# Oscillator.net
KiCad netlist of a schematic drawn in Altium Designer
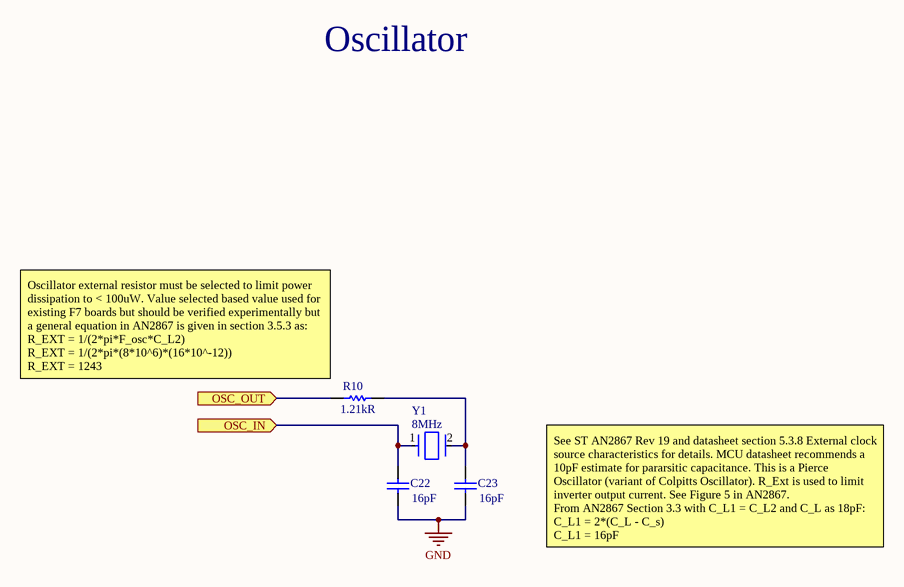
[diagram p0: Oscillator.SchDoc]

(export (version "E")
  (design (tool "Eeschema 10.0.6"))
  (components
    (comp (ref "C22")
      (value "06035A160JAT2A")
      (footprint "CAPC1608X90X35ML15T15")
      (fields (field (name "MANUFACTURER") "AVX Interconnect / Elco") (field (name "CAPACITANCE") "16pF"))
      (libsource (lib "Altium Content Vault") (part "CAP"))
    )
    (comp (ref "C23")
      (value "06035A160JAT2A")
      (footprint "CAPC1608X90X35ML15T15")
      (fields (field (name "MANUFACTURER") "AVX Interconnect / Elco") (field (name "CAPACITANCE") "16pF"))
      (libsource (lib "Altium Content Vault") (part "CAP"))
    )
    (comp (ref "R10")
      (value "CR0402-FX-1211GLF")
      (footprint "RESC1005X40X25NL10T10")
      (fields (field (name "MANUFACTURER") "Bourns") (field (name "RESISTANCE") "1.21kR"))
      (libsource (lib "Altium Content Vault") (part "RES"))
    )
    (comp (ref "Y1")
      (value "ABM3-8.000MHZ-D2Y-T")
      (footprint "FP-ABM3-MFG")
      (description "Crystal 8MHz ±20ppm 18pF SMD-2 5mm x 3.2mm")
      (fields (field (name "TOLERANCE") "20ppm") (field (name "FREQUENCY") "8MHz"))
      (libsource (lib "Altium Content Vault") (part "c23a69dc6c9e2f18f2079038eb95dd1"))
    )
  )
  (nets
    (net (code "1") (name "/OSC_IN") (class "Default")
      (node (ref "C22") (pin "2") (pinfunction "2_2") (pintype "passive"))
      (node (ref "Y1") (pin "1") (pinfunction "1_1") (pintype "passive"))
    )
    (net (code "2") (name "/OSC_OUT") (class "Default")
      (node (ref "R10") (pin "1") (pinfunction "1_1") (pintype "passive"))
    )
    (net (code "3") (name "GND") (class "Default")
      (node (ref "C22") (pin "1") (pinfunction "1_1") (pintype "passive"))
      (node (ref "C23") (pin "1") (pinfunction "1_1") (pintype "passive"))
    )
    (net (code "4") (name "Net-(C23-Pad2)") (class "Default")
      (node (ref "C23") (pin "2") (pinfunction "2_2") (pintype "passive"))
      (node (ref "R10") (pin "2") (pinfunction "2_2") (pintype "passive"))
      (node (ref "Y1") (pin "2") (pinfunction "2_2") (pintype "passive"))
    )
  )
)
